# stamp-fixed-mk-4_1.net
KiCad netlist of a schematic drawn in EAGLE
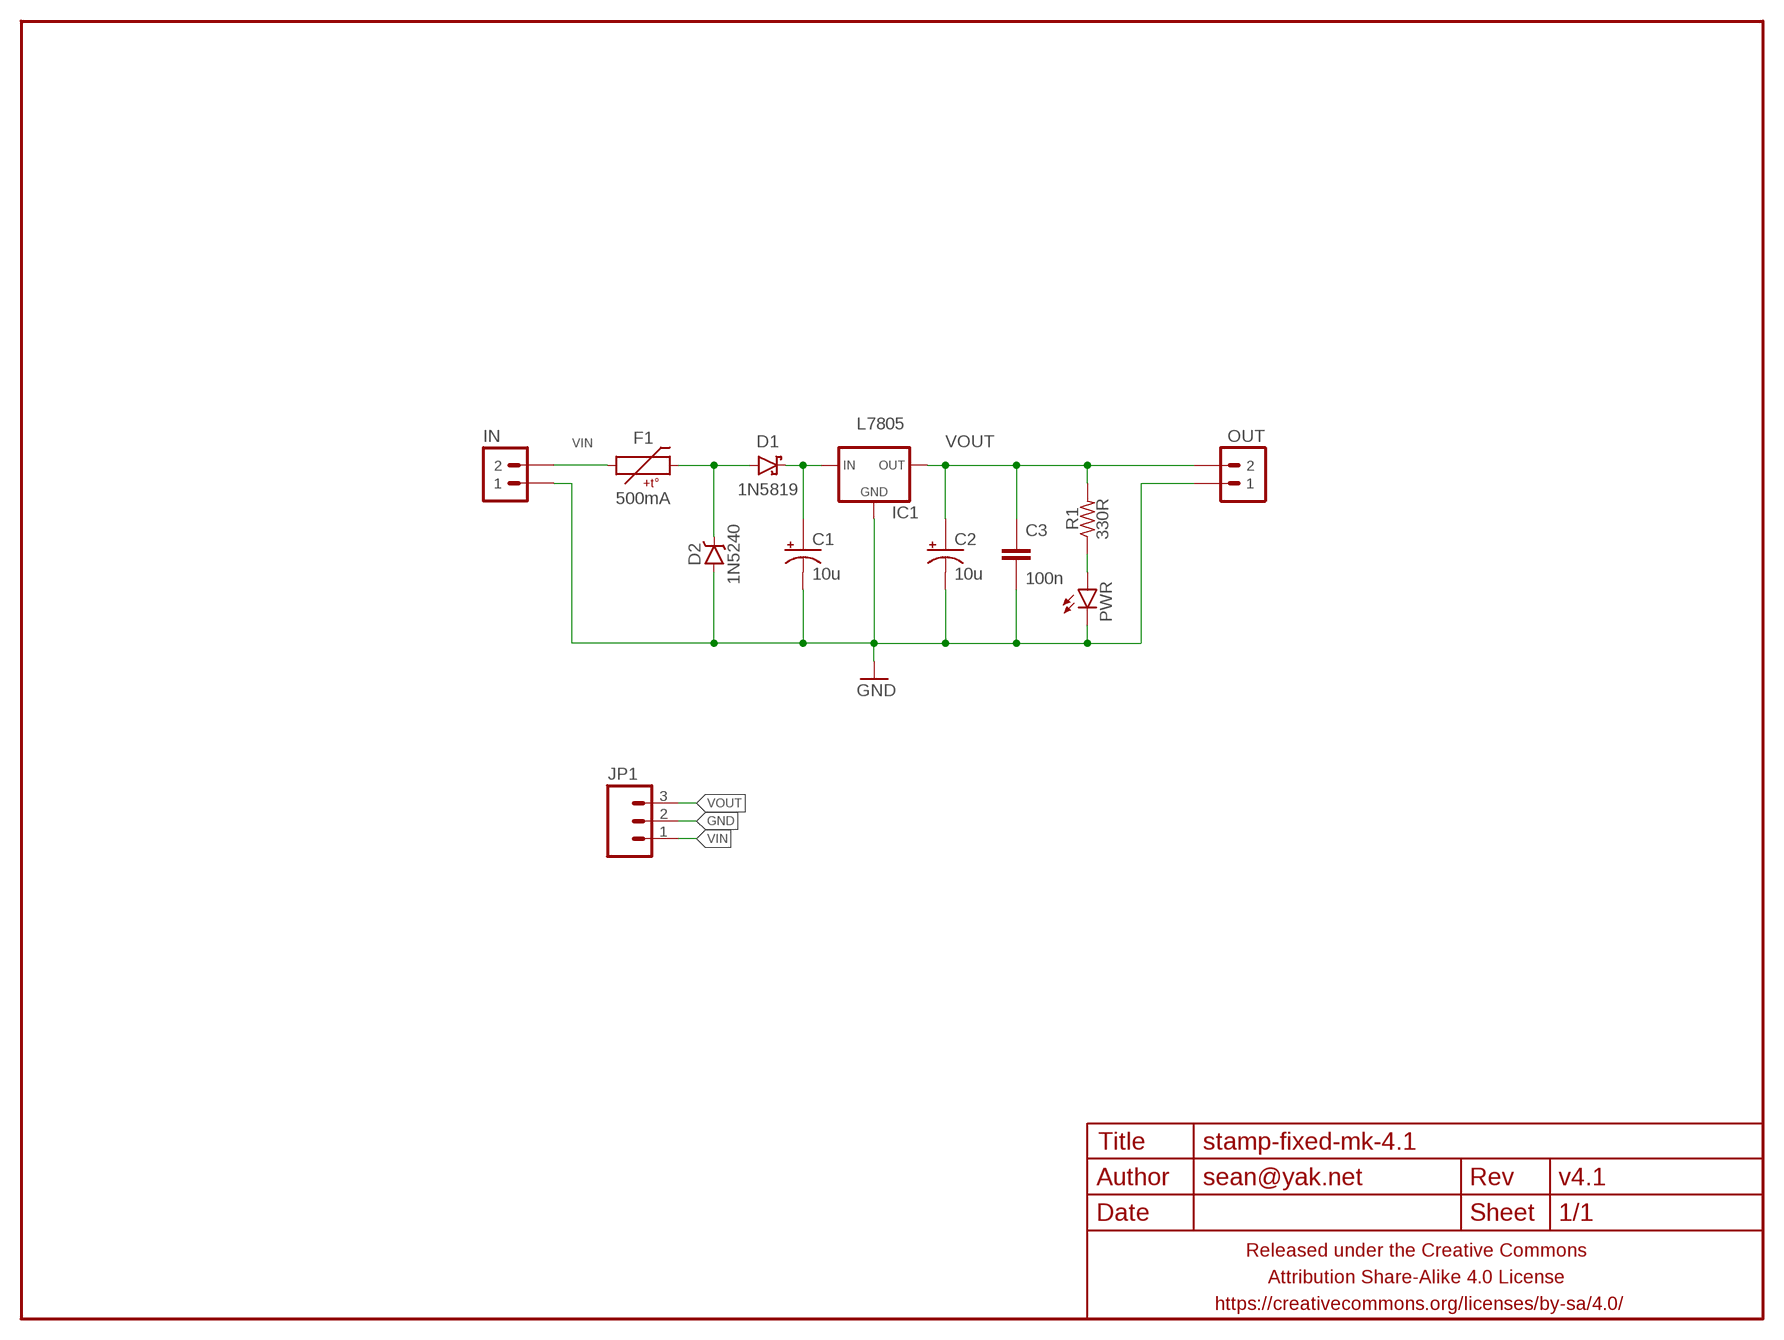
[diagram p0: schematic, sheet 1]

(export (version "E")
  (design (tool "Eeschema 10.0.6"))
  (components
    (comp (ref "C1")
      (value "10u")
      (footprint "eagle-import:E2,5-5")
      (libsource (lib "eagle-import") (part "CAPACITOR-POLARIZEDE2.5-5"))
    )
    (comp (ref "C2")
      (value "10u")
      (footprint "eagle-import:E2,5-5")
      (libsource (lib "eagle-import") (part "CAPACITOR-POLARIZEDE2.5-5"))
    )
    (comp (ref "C3")
      (value "100n")
      (footprint "eagle-import:C025-024X044")
      (libsource (lib "eagle-import") (part "CAPACITOR-CERAMIC025-024X044"))
    )
    (comp (ref "D1")
      (value "1N5819")
      (footprint "eagle-import:DIODE-SCHOTTKY-10.16MM")
      (libsource (lib "eagle-import") (part "DIODE-SCHOTTKYPTH-10.16MM"))
    )
    (comp (ref "D2")
      (value "1N5240")
      (footprint "eagle-import:DIODE-ZENNER-10.16MM")
      (libsource (lib "eagle-import") (part "DIODE-ZENER10.16MM-PTH"))
    )
    (comp (ref "F1")
      (value "500mA")
      (footprint "eagle-import:PTC-PTH-5.08MM")
      (libsource (lib "eagle-import") (part "PTCPTH-5.08MM"))
    )
    (comp (ref "FRAME1")
      (value "FRAME-LETTERNO_PACKAGE")
      (footprint "eagle-import:DUMMY")
      (fields (field (name "DESIGNER") "sean@yak.net") (field (name "VERSION") "v4.1"))
      (libsource (lib "eagle-import") (part "FRAME-LETTERNO_PACKAGE"))
    )
    (comp (ref "IC1")
      (value "L7805")
      (footprint "eagle-import:TO220-IGO-THERMPAD")
      (libsource (lib "eagle-import") (part "V_REG_78XXTO-220-THERMPAD"))
    )
    (comp (ref "IN")
      (value "M02PTH-CENTERED-R+")
      (footprint "eagle-import:1X02-CENTER-R+")
      (libsource (lib "eagle-import") (part "M02PTH-CENTERED-R+"))
    )
    (comp (ref "JP1")
      (value "M03PTH-CENTERED")
      (footprint "eagle-import:1X03-CENTERED")
      (libsource (lib "eagle-import") (part "M03PTH-CENTERED"))
    )
    (comp (ref "OUT")
      (value "M02PTH-CENTERED-R+")
      (footprint "eagle-import:1X02-CENTER-R+")
      (libsource (lib "eagle-import") (part "M02PTH-CENTERED-R+"))
    )
    (comp (ref "PWR")
      (value "LED3MM-LESS")
      (footprint "eagle-import:LED3MM-LESSSILK")
      (libsource (lib "eagle-import") (part "LED3MM-LESS"))
    )
    (comp (ref "R1")
      (value "330R")
      (footprint "eagle-import:RESISTOR-AXIAL-PTH-5.08MM")
      (libsource (lib "eagle-import") (part "RESISTORPTH-AXIAL-5.08MM"))
    )
  )
  (nets
    (net (code "1") (name "GND") (class "Default")
      (node (ref "C1") (pin "-") (pinfunction "-_-") (pintype "passive"))
      (node (ref "C2") (pin "-") (pinfunction "-_-") (pintype "passive"))
      (node (ref "C3") (pin "2") (pinfunction "2_2") (pintype "passive"))
      (node (ref "D2") (pin "A") (pinfunction "A_A") (pintype "passive"))
      (node (ref "IC1") (pin "4") (pinfunction "GND_4") (pintype "bidirectional"))
      (node (ref "IC1") (pin "GND") (pinfunction "GND_GND") (pintype "bidirectional"))
      (node (ref "IN") (pin "1") (pinfunction "1_1") (pintype "passive"))
      (node (ref "JP1") (pin "2") (pinfunction "2_2") (pintype "passive"))
      (node (ref "OUT") (pin "1") (pinfunction "1_1") (pintype "passive"))
      (node (ref "PWR") (pin "K") (pinfunction "C_K") (pintype "passive"))
    )
    (net (code "2") (name "Net-(C1-Pad+)") (class "Default")
      (node (ref "C1") (pin "+") (pinfunction "+_+") (pintype "passive"))
      (node (ref "D1") (pin "C") (pinfunction "C_C") (pintype "passive"))
      (node (ref "IC1") (pin "IN") (pinfunction "IN_IN") (pintype "bidirectional"))
    )
    (net (code "3") (name "Net-(D2-C)") (class "Default")
      (node (ref "D1") (pin "A") (pinfunction "A_A") (pintype "passive"))
      (node (ref "D2") (pin "K") (pinfunction "C_K") (pintype "passive"))
      (node (ref "F1") (pin "P$2") (pinfunction "2_P$2") (pintype "passive"))
    )
    (net (code "4") (name "Net-(R1-1)") (class "Default")
      (node (ref "PWR") (pin "A") (pinfunction "A_A") (pintype "passive"))
      (node (ref "R1") (pin "P$1") (pinfunction "1_P$1") (pintype "passive"))
    )
    (net (code "5") (name "VIN") (class "Default")
      (node (ref "F1") (pin "P$1") (pinfunction "1_P$1") (pintype "passive"))
      (node (ref "IN") (pin "2") (pinfunction "2_2") (pintype "passive"))
      (node (ref "JP1") (pin "1") (pinfunction "1_1") (pintype "passive"))
    )
    (net (code "6") (name "VOUT") (class "Default")
      (node (ref "C2") (pin "+") (pinfunction "+_+") (pintype "passive"))
      (node (ref "C3") (pin "1") (pinfunction "1_1") (pintype "passive"))
      (node (ref "IC1") (pin "OUT") (pinfunction "OUT_OUT") (pintype "bidirectional"))
      (node (ref "JP1") (pin "3") (pinfunction "3_3") (pintype "passive"))
      (node (ref "OUT") (pin "2") (pinfunction "2_2") (pintype "passive"))
      (node (ref "R1") (pin "P$2") (pinfunction "2_P$2") (pintype "passive"))
    )
  )
)
